# 01-MCU.net
KiCad netlist of a schematic drawn in Altium Designer
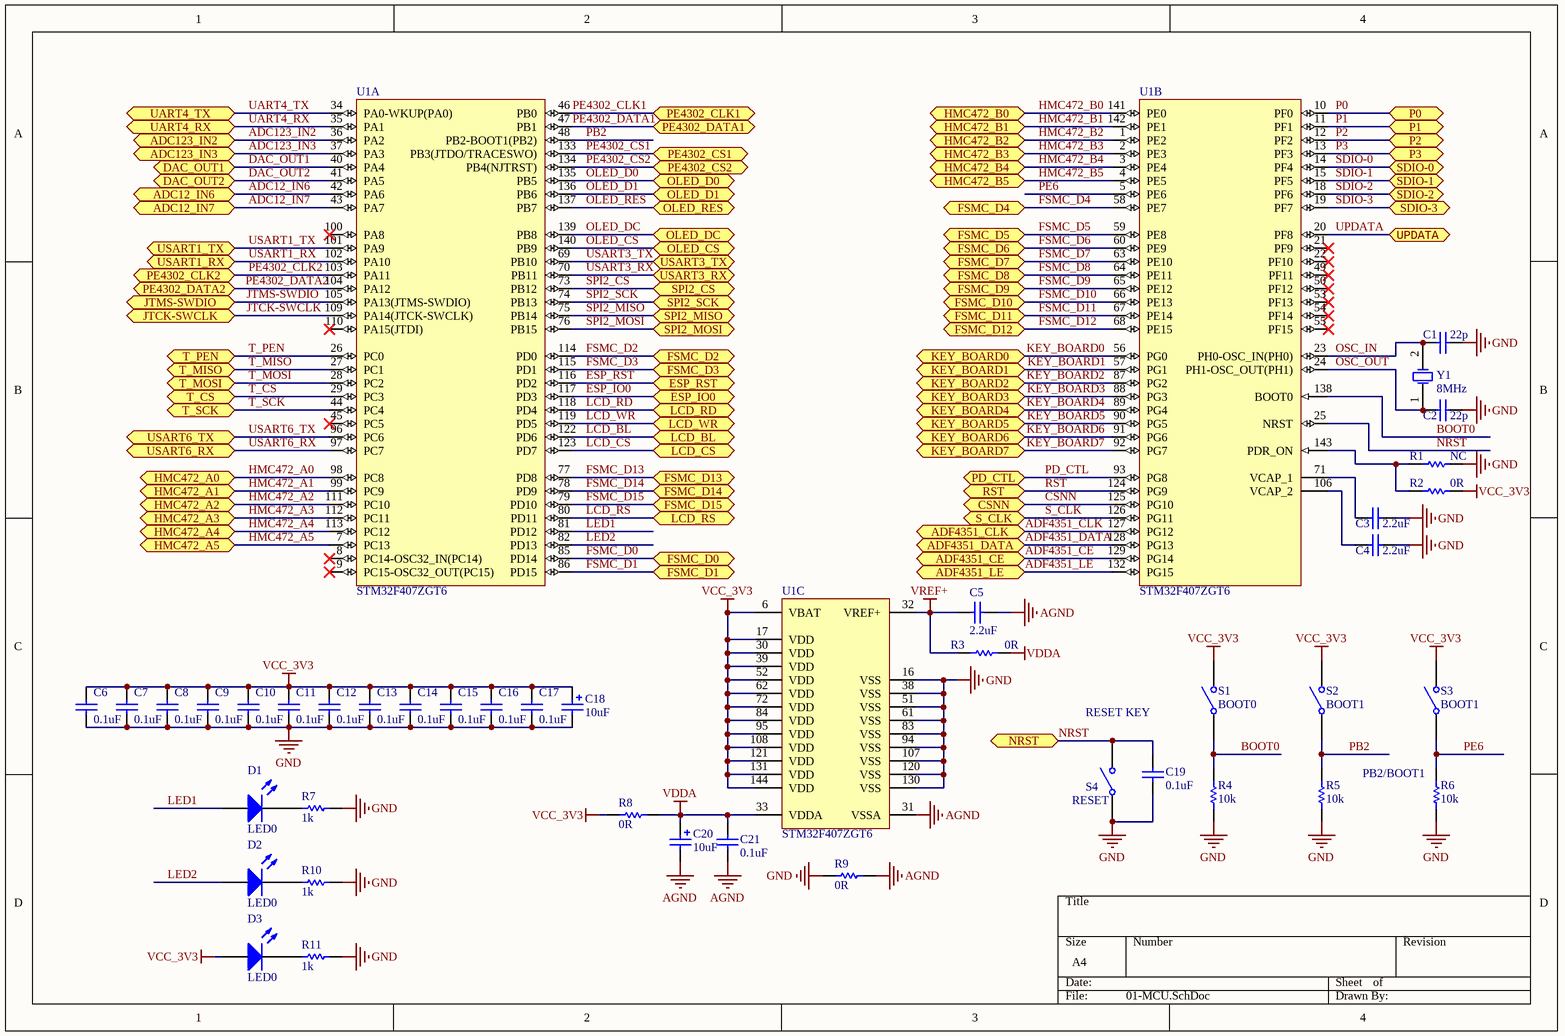
[diagram p0: 01-MCU.SchDoc]

(export (version "E")
  (design (tool "Eeschema 10.0.6"))
  (components
    (comp (ref "C1")
      (value "22p")
      (footprint "0603C")
      (description "CAP CER 10000PF 100V X7R 0603")
      (fields
        (field (name "MANUFACTURER") "TDK Corporation")
        (field (name "MANUFACTURER PART NUMBER") "C1608X7R2A103K080AA")
      )
      (libsource (lib "Desiger_Schlib") (part "Cap1"))
    )
    (comp (ref "C2")
      (value "22p")
      (footprint "0603C")
      (description "CAP CER 10000PF 100V X7R 0603")
      (fields
        (field (name "MANUFACTURER") "TDK Corporation")
        (field (name "MANUFACTURER PART NUMBER") "C1608X7R2A103K080AA")
      )
      (libsource (lib "Desiger_Schlib") (part "Cap1"))
    )
    (comp (ref "C3")
      (value "2.2uF")
      (footprint "0603C")
      (description "CAP CER 10000PF 100V X7R 0603")
      (fields
        (field (name "MANUFACTURER") "TDK Corporation")
        (field (name "MANUFACTURER PART NUMBER") "C1608X7R2A103K080AA")
      )
      (libsource (lib "Desiger_Schlib") (part "Cap1"))
    )
    (comp (ref "C4")
      (value "2.2uF")
      (footprint "0603C")
      (description "CAP CER 10000PF 100V X7R 0603")
      (fields
        (field (name "MANUFACTURER") "TDK Corporation")
        (field (name "MANUFACTURER PART NUMBER") "C1608X7R2A103K080AA")
      )
      (libsource (lib "Desiger_Schlib") (part "Cap1"))
    )
    (comp (ref "C5")
      (value "2.2uF")
      (footprint "0603C")
      (description "CAP CER 10000PF 100V X7R 0603")
      (fields
        (field (name "MANUFACTURER") "TDK Corporation")
        (field (name "MANUFACTURER PART NUMBER") "C1608X7R2A103K080AA")
      )
      (libsource (lib "Desiger_Schlib") (part "Cap1"))
    )
    (comp (ref "C6")
      (value "0.1uF")
      (footprint "0603C")
      (description "CAP CER 10000PF 100V X7R 0603")
      (fields
        (field (name "MANUFACTURER") "TDK Corporation")
        (field (name "MANUFACTURER PART NUMBER") "C1608X7R2A103K080AA")
      )
      (libsource (lib "Desiger_Schlib") (part "Cap1"))
    )
    (comp (ref "C7")
      (value "0.1uF")
      (footprint "0603C")
      (description "CAP CER 10000PF 100V X7R 0603")
      (fields
        (field (name "MANUFACTURER") "TDK Corporation")
        (field (name "MANUFACTURER PART NUMBER") "C1608X7R2A103K080AA")
      )
      (libsource (lib "Desiger_Schlib") (part "Cap1"))
    )
    (comp (ref "C8")
      (value "0.1uF")
      (footprint "0603C")
      (description "CAP CER 10000PF 100V X7R 0603")
      (fields
        (field (name "MANUFACTURER") "TDK Corporation")
        (field (name "MANUFACTURER PART NUMBER") "C1608X7R2A103K080AA")
      )
      (libsource (lib "Desiger_Schlib") (part "Cap1"))
    )
    (comp (ref "C9")
      (value "0.1uF")
      (footprint "0603C")
      (description "CAP CER 10000PF 100V X7R 0603")
      (fields
        (field (name "MANUFACTURER") "TDK Corporation")
        (field (name "MANUFACTURER PART NUMBER") "C1608X7R2A103K080AA")
      )
      (libsource (lib "Desiger_Schlib") (part "Cap1"))
    )
    (comp (ref "C10")
      (value "0.1uF")
      (footprint "0603C")
      (description "CAP CER 10000PF 100V X7R 0603")
      (fields
        (field (name "MANUFACTURER") "TDK Corporation")
        (field (name "MANUFACTURER PART NUMBER") "C1608X7R2A103K080AA")
      )
      (libsource (lib "Desiger_Schlib") (part "Cap1"))
    )
    (comp (ref "C11")
      (value "0.1uF")
      (footprint "0603C")
      (description "CAP CER 10000PF 100V X7R 0603")
      (fields
        (field (name "MANUFACTURER") "TDK Corporation")
        (field (name "MANUFACTURER PART NUMBER") "C1608X7R2A103K080AA")
      )
      (libsource (lib "Desiger_Schlib") (part "Cap1"))
    )
    (comp (ref "C12")
      (value "0.1uF")
      (footprint "0603C")
      (description "CAP CER 10000PF 100V X7R 0603")
      (fields
        (field (name "MANUFACTURER") "TDK Corporation")
        (field (name "MANUFACTURER PART NUMBER") "C1608X7R2A103K080AA")
      )
      (libsource (lib "Desiger_Schlib") (part "Cap1"))
    )
    (comp (ref "C13")
      (value "0.1uF")
      (footprint "0603C")
      (description "CAP CER 10000PF 100V X7R 0603")
      (fields
        (field (name "MANUFACTURER") "TDK Corporation")
        (field (name "MANUFACTURER PART NUMBER") "C1608X7R2A103K080AA")
      )
      (libsource (lib "Desiger_Schlib") (part "Cap1"))
    )
    (comp (ref "C14")
      (value "0.1uF")
      (footprint "0603C")
      (description "CAP CER 10000PF 100V X7R 0603")
      (fields
        (field (name "MANUFACTURER") "TDK Corporation")
        (field (name "MANUFACTURER PART NUMBER") "C1608X7R2A103K080AA")
      )
      (libsource (lib "Desiger_Schlib") (part "Cap1"))
    )
    (comp (ref "C15")
      (value "0.1uF")
      (footprint "0603C")
      (description "CAP CER 10000PF 100V X7R 0603")
      (fields
        (field (name "MANUFACTURER") "TDK Corporation")
        (field (name "MANUFACTURER PART NUMBER") "C1608X7R2A103K080AA")
      )
      (libsource (lib "Desiger_Schlib") (part "Cap1"))
    )
    (comp (ref "C16")
      (value "0.1uF")
      (footprint "0603C")
      (description "CAP CER 10000PF 100V X7R 0603")
      (fields
        (field (name "MANUFACTURER") "TDK Corporation")
        (field (name "MANUFACTURER PART NUMBER") "C1608X7R2A103K080AA")
      )
      (libsource (lib "Desiger_Schlib") (part "Cap1"))
    )
    (comp (ref "C17")
      (value "0.1uF")
      (footprint "0603C")
      (description "CAP CER 10000PF 100V X7R 0603")
      (fields
        (field (name "MANUFACTURER") "TDK Corporation")
        (field (name "MANUFACTURER PART NUMBER") "C1608X7R2A103K080AA")
      )
      (libsource (lib "Desiger_Schlib") (part "Cap1"))
    )
    (comp (ref "C18")
      (value "10uF")
      (footprint "1206T")
      (description "CAP TANT 10UF 10V 10% 1206")
      (fields
        (field (name "MANUFACTURER") "KEMET")
        (field (name "MANUFACTURER PART NUMBER") "T491A106K010AT7280")
      )
      (libsource (lib "Desiger_Schlib") (part "Cap2"))
    )
    (comp (ref "C19")
      (value "0.1uF")
      (footprint "0603C")
      (description "CAP CER 10000PF 100V X7R 0603")
      (fields
        (field (name "MANUFACTURER") "TDK Corporation")
        (field (name "MANUFACTURER PART NUMBER") "C1608X7R2A103K080AA")
      )
      (libsource (lib "Desiger_Schlib") (part "Cap1"))
    )
    (comp (ref "C20")
      (value "10uF")
      (footprint "1206T")
      (description "CAP TANT 10UF 10V 10% 1206")
      (fields
        (field (name "MANUFACTURER") "KEMET")
        (field (name "MANUFACTURER PART NUMBER") "T491A106K010AT7280")
      )
      (libsource (lib "Desiger_Schlib") (part "Cap2"))
    )
    (comp (ref "C21")
      (value "0.1uF")
      (footprint "0603C")
      (description "CAP CER 10000PF 100V X7R 0603")
      (fields
        (field (name "MANUFACTURER") "TDK Corporation")
        (field (name "MANUFACTURER PART NUMBER") "C1608X7R2A103K080AA")
      )
      (libsource (lib "Desiger_Schlib") (part "Cap1"))
    )
    (comp (ref "D1")
      (value "LED0")
      (footprint "0603D")
      (description "Typical INFRARED GaAs LED")
      (fields (field (name "PUBLISHER") "Altium Limited"))
      (libsource (lib "Miscellaneous Devices") (part "LED0"))
    )
    (comp (ref "D2")
      (value "LED0")
      (footprint "0603D")
      (description "Typical INFRARED GaAs LED")
      (fields (field (name "PUBLISHER") "Altium Limited"))
      (libsource (lib "Miscellaneous Devices") (part "LED0"))
    )
    (comp (ref "D3")
      (value "LED0")
      (footprint "0603D")
      (description "Typical INFRARED GaAs LED")
      (fields (field (name "PUBLISHER") "Altium Limited"))
      (libsource (lib "Miscellaneous Devices") (part "LED0"))
    )
    (comp (ref "R1")
      (value "NC")
      (footprint "0603R")
      (description "RES SMD 1K OHM 0.5% 1/16W 0603")
      (fields
        (field (name "MANUFACTURER") "Susumu")
        (field (name "MANUFACTURER PART NUMBER") "RR0816P-102-D")
      )
      (libsource (lib "Desiger_Schlib") (part "Res1"))
    )
    (comp (ref "R2")
      (value "0R")
      (footprint "0603R")
      (description "RES SMD 1K OHM 0.5% 1/16W 0603")
      (fields
        (field (name "MANUFACTURER") "Susumu")
        (field (name "MANUFACTURER PART NUMBER") "RR0816P-102-D")
      )
      (libsource (lib "Desiger_Schlib") (part "Res1"))
    )
    (comp (ref "R3")
      (value "0R")
      (footprint "0603R")
      (description "RES SMD 1K OHM 0.5% 1/16W 0603")
      (fields
        (field (name "MANUFACTURER") "Susumu")
        (field (name "MANUFACTURER PART NUMBER") "RR0816P-102-D")
      )
      (libsource (lib "Desiger_Schlib") (part "Res1"))
    )
    (comp (ref "R4")
      (value "10k")
      (footprint "0603R")
      (description "RES SMD 1K OHM 0.5% 1/16W 0603")
      (fields
        (field (name "MANUFACTURER") "Susumu")
        (field (name "MANUFACTURER PART NUMBER") "RR0816P-102-D")
      )
      (libsource (lib "Desiger_Schlib") (part "Res1"))
    )
    (comp (ref "R5")
      (value "10k")
      (footprint "0603R")
      (description "RES SMD 1K OHM 0.5% 1/16W 0603")
      (fields
        (field (name "MANUFACTURER") "Susumu")
        (field (name "MANUFACTURER PART NUMBER") "RR0816P-102-D")
      )
      (libsource (lib "Desiger_Schlib") (part "Res1"))
    )
    (comp (ref "R6")
      (value "10k")
      (footprint "0603R")
      (description "RES SMD 1K OHM 0.5% 1/16W 0603")
      (fields
        (field (name "MANUFACTURER") "Susumu")
        (field (name "MANUFACTURER PART NUMBER") "RR0816P-102-D")
      )
      (libsource (lib "Desiger_Schlib") (part "Res1"))
    )
    (comp (ref "R7")
      (value "1k")
      (footprint "0603R")
      (description "RES SMD 1K OHM 0.5% 1/16W 0603")
      (fields
        (field (name "MANUFACTURER") "Susumu")
        (field (name "MANUFACTURER PART NUMBER") "RR0816P-102-D")
      )
      (libsource (lib "Desiger_Schlib") (part "Res1"))
    )
    (comp (ref "R8")
      (value "0R")
      (footprint "0603R")
      (description "RES SMD 1K OHM 0.5% 1/16W 0603")
      (fields
        (field (name "MANUFACTURER") "Susumu")
        (field (name "MANUFACTURER PART NUMBER") "RR0816P-102-D")
      )
      (libsource (lib "Desiger_Schlib") (part "Res1"))
    )
    (comp (ref "R9")
      (value "0R")
      (footprint "0603R")
      (description "RES SMD 1K OHM 0.5% 1/16W 0603")
      (fields
        (field (name "MANUFACTURER") "Susumu")
        (field (name "MANUFACTURER PART NUMBER") "RR0816P-102-D")
      )
      (libsource (lib "Desiger_Schlib") (part "Res1"))
    )
    (comp (ref "R10")
      (value "1k")
      (footprint "0603R")
      (description "RES SMD 1K OHM 0.5% 1/16W 0603")
      (fields
        (field (name "MANUFACTURER") "Susumu")
        (field (name "MANUFACTURER PART NUMBER") "RR0816P-102-D")
      )
      (libsource (lib "Desiger_Schlib") (part "Res1"))
    )
    (comp (ref "R11")
      (value "1k")
      (footprint "0603R")
      (description "RES SMD 1K OHM 0.5% 1/16W 0603")
      (fields
        (field (name "MANUFACTURER") "Susumu")
        (field (name "MANUFACTURER PART NUMBER") "RR0816P-102-D")
      )
      (libsource (lib "Desiger_Schlib") (part "Res1"))
    )
    (comp (ref "S1")
      (value "BOOT0")
      (footprint "micro button_2_SMD")
      (description "Single-Pole, Single-Throw Switch")
      (fields (field (name "PUBLISHER") "Altium Limited"))
      (libsource (lib "Miscellaneous Devices") (part "SW-SPST"))
    )
    (comp (ref "S2")
      (value "BOOT1")
      (footprint "micro button_2_SMD")
      (description "Single-Pole, Single-Throw Switch")
      (fields (field (name "PUBLISHER") "Altium Limited"))
      (libsource (lib "Miscellaneous Devices") (part "SW-SPST"))
    )
    (comp (ref "S3")
      (value "BOOT1")
      (footprint "micro button_2_SMD")
      (description "Single-Pole, Single-Throw Switch")
      (fields (field (name "PUBLISHER") "Altium Limited"))
      (libsource (lib "Miscellaneous Devices") (part "SW-SPST"))
    )
    (comp (ref "S4")
      (value "RESET")
      (footprint "micro button_2_SMD")
      (description "Single-Pole, Single-Throw Switch")
      (fields (field (name "PUBLISHER") "Altium Limited"))
      (libsource (lib "Miscellaneous Devices") (part "SW-SPST"))
    )
    (comp (ref "U1")
      (value "STM32F407ZGT6")
      (footprint "QFP144-0r5-20X20")
      (fields (field (name "MANUFACTURER") "STMicroelectronics"))
      (libsource (lib "STMicroelectronics STM32 F4") (part "STM32F407ZGT6"))
    )
    (comp (ref "Y1")
      (value "8MHz")
      (footprint "CO2-4R75X11R4-S")
      (description "Crystal Oscillator")
      (fields (field (name "PUBLISHER") "Altium Limited"))
      (libsource (lib "Miscellaneous Devices") (part "XTAL"))
    )
  )
  (nets
    (net (code "1") (name "/ADC12_IN6") (class "Default")
      (node (ref "U1") (pin "42") (pinfunction "PA6_42") (pintype "bidirectional"))
    )
    (net (code "2") (name "/ADC12_IN7") (class "Default")
      (node (ref "U1") (pin "43") (pinfunction "PA7_43") (pintype "bidirectional"))
    )
    (net (code "3") (name "/ADC123_IN2") (class "Default")
      (node (ref "U1") (pin "36") (pinfunction "PA2_36") (pintype "bidirectional"))
    )
    (net (code "4") (name "/ADC123_IN3") (class "Default")
      (node (ref "U1") (pin "37") (pinfunction "PA3_37") (pintype "bidirectional"))
    )
    (net (code "5") (name "/ADF4351_CE") (class "Default")
      (node (ref "U1") (pin "129") (pinfunction "PG14_129") (pintype "bidirectional"))
    )
    (net (code "6") (name "/ADF4351_CLK") (class "Default")
      (node (ref "U1") (pin "127") (pinfunction "PG12_127") (pintype "bidirectional"))
    )
    (net (code "7") (name "/ADF4351_DATA") (class "Default")
      (node (ref "U1") (pin "128") (pinfunction "PG13_128") (pintype "bidirectional"))
    )
    (net (code "8") (name "/ADF4351_LE") (class "Default")
      (node (ref "U1") (pin "132") (pinfunction "PG15_132") (pintype "bidirectional"))
    )
    (net (code "9") (name "/BOOT0") (class "Default")
      (node (ref "R4") (pin "2") (pinfunction "2_2") (pintype "passive"))
      (node (ref "S1") (pin "1") (pinfunction "COMMON_1") (pintype "passive"))
      (node (ref "U1") (pin "138") (pinfunction "BOOT0_138") (pintype "input"))
    )
    (net (code "10") (name "/CSNN") (class "Default")
      (node (ref "U1") (pin "125") (pinfunction "PG10_125") (pintype "bidirectional"))
    )
    (net (code "11") (name "/DAC_OUT1") (class "Default")
      (node (ref "U1") (pin "40") (pinfunction "PA4_40") (pintype "bidirectional"))
    )
    (net (code "12") (name "/DAC_OUT2") (class "Default")
      (node (ref "U1") (pin "41") (pinfunction "PA5_41") (pintype "bidirectional"))
    )
    (net (code "13") (name "/ESP_IO0") (class "Default")
      (node (ref "U1") (pin "117") (pinfunction "PD3_117") (pintype "bidirectional"))
    )
    (net (code "14") (name "/ESP_RST") (class "Default")
      (node (ref "U1") (pin "116") (pinfunction "PD2_116") (pintype "bidirectional"))
    )
    (net (code "15") (name "/FSMC_D0") (class "Default")
      (node (ref "U1") (pin "85") (pinfunction "PD14_85") (pintype "bidirectional"))
    )
    (net (code "16") (name "/FSMC_D1") (class "Default")
      (node (ref "U1") (pin "86") (pinfunction "PD15_86") (pintype "bidirectional"))
    )
    (net (code "17") (name "/FSMC_D2") (class "Default")
      (node (ref "U1") (pin "114") (pinfunction "PD0_114") (pintype "bidirectional"))
    )
    (net (code "18") (name "/FSMC_D3") (class "Default")
      (node (ref "U1") (pin "115") (pinfunction "PD1_115") (pintype "bidirectional"))
    )
    (net (code "19") (name "/FSMC_D4") (class "Default")
      (node (ref "U1") (pin "58") (pinfunction "PE7_58") (pintype "bidirectional"))
    )
    (net (code "20") (name "/FSMC_D5") (class "Default")
      (node (ref "U1") (pin "59") (pinfunction "PE8_59") (pintype "bidirectional"))
    )
    (net (code "21") (name "/FSMC_D6") (class "Default")
      (node (ref "U1") (pin "60") (pinfunction "PE9_60") (pintype "bidirectional"))
    )
    (net (code "22") (name "/FSMC_D7") (class "Default")
      (node (ref "U1") (pin "63") (pinfunction "PE10_63") (pintype "bidirectional"))
    )
    (net (code "23") (name "/FSMC_D8") (class "Default")
      (node (ref "U1") (pin "64") (pinfunction "PE11_64") (pintype "bidirectional"))
    )
    (net (code "24") (name "/FSMC_D9") (class "Default")
      (node (ref "U1") (pin "65") (pinfunction "PE12_65") (pintype "bidirectional"))
    )
    (net (code "25") (name "/FSMC_D10") (class "Default")
      (node (ref "U1") (pin "66") (pinfunction "PE13_66") (pintype "bidirectional"))
    )
    (net (code "26") (name "/FSMC_D11") (class "Default")
      (node (ref "U1") (pin "67") (pinfunction "PE14_67") (pintype "bidirectional"))
    )
    (net (code "27") (name "/FSMC_D12") (class "Default")
      (node (ref "U1") (pin "68") (pinfunction "PE15_68") (pintype "bidirectional"))
    )
    (net (code "28") (name "/FSMC_D13") (class "Default")
      (node (ref "U1") (pin "77") (pinfunction "PD8_77") (pintype "bidirectional"))
    )
    (net (code "29") (name "/FSMC_D14") (class "Default")
      (node (ref "U1") (pin "78") (pinfunction "PD9_78") (pintype "bidirectional"))
    )
    (net (code "30") (name "/FSMC_D15") (class "Default")
      (node (ref "U1") (pin "79") (pinfunction "PD10_79") (pintype "bidirectional"))
    )
    (net (code "31") (name "/HMC472_A0") (class "Default")
      (node (ref "U1") (pin "98") (pinfunction "PC8_98") (pintype "bidirectional"))
    )
    (net (code "32") (name "/HMC472_A1") (class "Default")
      (node (ref "U1") (pin "99") (pinfunction "PC9_99") (pintype "bidirectional"))
    )
    (net (code "33") (name "/HMC472_A2") (class "Default")
      (node (ref "U1") (pin "111") (pinfunction "PC10_111") (pintype "bidirectional"))
    )
    (net (code "34") (name "/HMC472_A3") (class "Default")
      (node (ref "U1") (pin "112") (pinfunction "PC11_112") (pintype "bidirectional"))
    )
    (net (code "35") (name "/HMC472_A4") (class "Default")
      (node (ref "U1") (pin "113") (pinfunction "PC12_113") (pintype "bidirectional"))
    )
    (net (code "36") (name "/HMC472_A5") (class "Default")
      (node (ref "U1") (pin "7") (pinfunction "PC13_7") (pintype "bidirectional"))
    )
    (net (code "37") (name "/HMC472_B0") (class "Default")
      (node (ref "U1") (pin "141") (pinfunction "PE0_141") (pintype "bidirectional"))
    )
    (net (code "38") (name "/HMC472_B1") (class "Default")
      (node (ref "U1") (pin "142") (pinfunction "PE1_142") (pintype "bidirectional"))
    )
    (net (code "39") (name "/HMC472_B2") (class "Default")
      (node (ref "U1") (pin "1") (pinfunction "PE2_1") (pintype "bidirectional"))
    )
    (net (code "40") (name "/HMC472_B3") (class "Default")
      (node (ref "U1") (pin "2") (pinfunction "PE3_2") (pintype "bidirectional"))
    )
    (net (code "41") (name "/HMC472_B4") (class "Default")
      (node (ref "U1") (pin "3") (pinfunction "PE4_3") (pintype "bidirectional"))
    )
    (net (code "42") (name "/HMC472_B5") (class "Default")
      (node (ref "U1") (pin "4") (pinfunction "PE5_4") (pintype "bidirectional"))
    )
    (net (code "43") (name "/JTCK-SWCLK") (class "Default")
      (node (ref "U1") (pin "109") (pinfunction "PA14(JTCK-SWCLK)_109") (pintype "bidirectional"))
    )
    (net (code "44") (name "/JTMS-SWDIO") (class "Default")
      (node (ref "U1") (pin "105") (pinfunction "PA13(JTMS-SWDIO)_105") (pintype "bidirectional"))
    )
    (net (code "45") (name "/KEY_BOARD0") (class "Default")
      (node (ref "U1") (pin "56") (pinfunction "PG0_56") (pintype "bidirectional"))
    )
    (net (code "46") (name "/KEY_BOARD1") (class "Default")
      (node (ref "U1") (pin "57") (pinfunction "PG1_57") (pintype "bidirectional"))
    )
    (net (code "47") (name "/KEY_BOARD2") (class "Default")
      (node (ref "U1") (pin "87") (pinfunction "PG2_87") (pintype "bidirectional"))
    )
    (net (code "48") (name "/KEY_BOARD3") (class "Default")
      (node (ref "U1") (pin "88") (pinfunction "PG3_88") (pintype "bidirectional"))
    )
    (net (code "49") (name "/KEY_BOARD4") (class "Default")
      (node (ref "U1") (pin "89") (pinfunction "PG4_89") (pintype "bidirectional"))
    )
    (net (code "50") (name "/KEY_BOARD5") (class "Default")
      (node (ref "U1") (pin "90") (pinfunction "PG5_90") (pintype "bidirectional"))
    )
    (net (code "51") (name "/KEY_BOARD6") (class "Default")
      (node (ref "U1") (pin "91") (pinfunction "PG6_91") (pintype "bidirectional"))
    )
    (net (code "52") (name "/KEY_BOARD7") (class "Default")
      (node (ref "U1") (pin "92") (pinfunction "PG7_92") (pintype "bidirectional"))
    )
    (net (code "53") (name "/LCD_BL") (class "Default")
      (node (ref "U1") (pin "122") (pinfunction "PD6_122") (pintype "bidirectional"))
    )
    (net (code "54") (name "/LCD_CS") (class "Default")
      (node (ref "U1") (pin "123") (pinfunction "PD7_123") (pintype "bidirectional"))
    )
    (net (code "55") (name "/LCD_RD") (class "Default")
      (node (ref "U1") (pin "118") (pinfunction "PD4_118") (pintype "bidirectional"))
    )
    (net (code "56") (name "/LCD_RS") (class "Default")
      (node (ref "U1") (pin "80") (pinfunction "PD11_80") (pintype "bidirectional"))
    )
    (net (code "57") (name "/LCD_WR") (class "Default")
      (node (ref "U1") (pin "119") (pinfunction "PD5_119") (pintype "bidirectional"))
    )
    (net (code "58") (name "/LED1") (class "Default")
      (node (ref "D1") (pin "1") (pinfunction "A_1") (pintype "passive"))
      (node (ref "U1") (pin "81") (pinfunction "PD12_81") (pintype "bidirectional"))
    )
    (net (code "59") (name "/LED2") (class "Default")
      (node (ref "D2") (pin "1") (pinfunction "A_1") (pintype "passive"))
      (node (ref "U1") (pin "82") (pinfunction "PD13_82") (pintype "bidirectional"))
    )
    (net (code "60") (name "/NRST") (class "Default")
      (node (ref "C19") (pin "2") (pinfunction "2_2") (pintype "passive"))
      (node (ref "S4") (pin "2") (pinfunction "NO_2") (pintype "passive"))
      (node (ref "U1") (pin "25") (pinfunction "NRST_25") (pintype "bidirectional"))
    )
    (net (code "61") (name "/OLED_CS") (class "Default")
      (node (ref "U1") (pin "140") (pinfunction "PB9_140") (pintype "bidirectional"))
    )
    (net (code "62") (name "/OLED_D0") (class "Default")
      (node (ref "U1") (pin "135") (pinfunction "PB5_135") (pintype "bidirectional"))
    )
    (net (code "63") (name "/OLED_D1") (class "Default")
      (node (ref "U1") (pin "136") (pinfunction "PB6_136") (pintype "bidirectional"))
    )
    (net (code "64") (name "/OLED_DC") (class "Default")
      (node (ref "U1") (pin "139") (pinfunction "PB8_139") (pintype "bidirectional"))
    )
    (net (code "65") (name "/OLED_RES") (class "Default")
      (node (ref "U1") (pin "137") (pinfunction "PB7_137") (pintype "bidirectional"))
    )
    (net (code "66") (name "/OSC_IN") (class "Default")
      (node (ref "C1") (pin "1") (pinfunction "1_1") (pintype "passive"))
      (node (ref "U1") (pin "23") (pinfunction "PH0-OSC_IN(PH0)_23") (pintype "bidirectional"))
      (node (ref "Y1") (pin "2") (pinfunction "OSC2_2") (pintype "passive"))
    )
    (net (code "67") (name "/OSC_OUT") (class "Default")
      (node (ref "C2") (pin "1") (pinfunction "1_1") (pintype "passive"))
      (node (ref "U1") (pin "24") (pinfunction "PH1-OSC_OUT(PH1)_24") (pintype "bidirectional"))
      (node (ref "Y1") (pin "1") (pinfunction "OSC1_1") (pintype "passive"))
    )
    (net (code "68") (name "/P0") (class "Default")
      (node (ref "U1") (pin "10") (pinfunction "PF0_10") (pintype "bidirectional"))
    )
    (net (code "69") (name "/P1") (class "Default")
      (node (ref "U1") (pin "11") (pinfunction "PF1_11") (pintype "bidirectional"))
    )
    (net (code "70") (name "/P2") (class "Default")
      (node (ref "U1") (pin "12") (pinfunction "PF2_12") (pintype "bidirectional"))
    )
    (net (code "71") (name "/P3") (class "Default")
      (node (ref "U1") (pin "13") (pinfunction "PF3_13") (pintype "bidirectional"))
    )
    (net (code "72") (name "/PB2") (class "Default")
      (node (ref "R5") (pin "2") (pinfunction "2_2") (pintype "passive"))
      (node (ref "S2") (pin "1") (pinfunction "COMMON_1") (pintype "passive"))
      (node (ref "U1") (pin "48") (pinfunction "PB2-BOOT1(PB2)_48") (pintype "bidirectional"))
    )
    (net (code "73") (name "/PD_CTL") (class "Default")
      (node (ref "U1") (pin "93") (pinfunction "PG8_93") (pintype "bidirectional"))
    )
    (net (code "74") (name "/PE6") (class "Default")
      (node (ref "R6") (pin "2") (pinfunction "2_2") (pintype "passive"))
      (node (ref "S3") (pin "1") (pinfunction "COMMON_1") (pintype "passive"))
      (node (ref "U1") (pin "5") (pinfunction "PE6_5") (pintype "bidirectional"))
    )
    (net (code "75") (name "/PE4302_CLK1") (class "Default")
      (node (ref "U1") (pin "46") (pinfunction "PB0_46") (pintype "bidirectional"))
    )
    (net (code "76") (name "/PE4302_CLK2") (class "Default")
      (node (ref "U1") (pin "103") (pinfunction "PA11_103") (pintype "bidirectional"))
    )
    (net (code "77") (name "/PE4302_CS1") (class "Default")
      (node (ref "U1") (pin "133") (pinfunction "PB3(JTDO/TRACESWO)_133") (pintype "bidirectional"))
    )
    (net (code "78") (name "/PE4302_CS2") (class "Default")
      (node (ref "U1") (pin "134") (pinfunction "PB4(NJTRST)_134") (pintype "bidirectional"))
    )
    (net (code "79") (name "/PE4302_DATA1") (class "Default")
      (node (ref "U1") (pin "47") (pinfunction "PB1_47") (pintype "bidirectional"))
    )
    (net (code "80") (name "/PE4302_DATA2") (class "Default")
      (node (ref "U1") (pin "104") (pinfunction "PA12_104") (pintype "bidirectional"))
    )
    (net (code "81") (name "/RST") (class "Default")
      (node (ref "U1") (pin "124") (pinfunction "PG9_124") (pintype "bidirectional"))
    )
    (net (code "82") (name "/SDIO-0") (class "Default")
      (node (ref "U1") (pin "14") (pinfunction "PF4_14") (pintype "bidirectional"))
    )
    (net (code "83") (name "/SDIO-1") (class "Default")
      (node (ref "U1") (pin "15") (pinfunction "PF5_15") (pintype "bidirectional"))
    )
    (net (code "84") (name "/SDIO-2") (class "Default")
      (node (ref "U1") (pin "18") (pinfunction "PF6_18") (pintype "bidirectional"))
    )
    (net (code "85") (name "/SDIO-3") (class "Default")
      (node (ref "U1") (pin "19") (pinfunction "PF7_19") (pintype "bidirectional"))
    )
    (net (code "86") (name "/SPI2_CS") (class "Default")
      (node (ref "U1") (pin "73") (pinfunction "PB12_73") (pintype "bidirectional"))
    )
    (net (code "87") (name "/SPI2_MISO") (class "Default")
      (node (ref "U1") (pin "75") (pinfunction "PB14_75") (pintype "bidirectional"))
    )
    (net (code "88") (name "/SPI2_MOSI") (class "Default")
      (node (ref "U1") (pin "76") (pinfunction "PB15_76") (pintype "bidirectional"))
    )
    (net (code "89") (name "/SPI2_SCK") (class "Default")
      (node (ref "U1") (pin "74") (pinfunction "PB13_74") (pintype "bidirectional"))
    )
    (net (code "90") (name "/S_CLK") (class "Default")
      (node (ref "U1") (pin "126") (pinfunction "PG11_126") (pintype "bidirectional"))
    )
    (net (code "91") (name "/T_CS") (class "Default")
      (node (ref "U1") (pin "29") (pinfunction "PC3_29") (pintype "bidirectional"))
    )
    (net (code "92") (name "/T_MISO") (class "Default")
      (node (ref "U1") (pin "27") (pinfunction "PC1_27") (pintype "bidirectional"))
    )
    (net (code "93") (name "/T_MOSI") (class "Default")
      (node (ref "U1") (pin "28") (pinfunction "PC2_28") (pintype "bidirectional"))
    )
    (net (code "94") (name "/T_PEN") (class "Default")
      (node (ref "U1") (pin "26") (pinfunction "PC0_26") (pintype "bidirectional"))
    )
    (net (code "95") (name "/T_SCK") (class "Default")
      (node (ref "U1") (pin "44") (pinfunction "PC4_44") (pintype "bidirectional"))
    )
    (net (code "96") (name "/UART4_RX") (class "Default")
      (node (ref "U1") (pin "35") (pinfunction "PA1_35") (pintype "bidirectional"))
    )
    (net (code "97") (name "/UART4_TX") (class "Default")
      (node (ref "U1") (pin "34") (pinfunction "PA0-WKUP(PA0)_34") (pintype "bidirectional"))
    )
    (net (code "98") (name "/UPDATA") (class "Default")
      (node (ref "U1") (pin "20") (pinfunction "PF8_20") (pintype "bidirectional"))
    )
    (net (code "99") (name "/USART1_RX") (class "Default")
      (node (ref "U1") (pin "102") (pinfunction "PA10_102") (pintype "bidirectional"))
    )
    (net (code "100") (name "/USART1_TX") (class "Default")
      (node (ref "U1") (pin "101") (pinfunction "PA9_101") (pintype "bidirectional"))
    )
    (net (code "101") (name "/USART3_RX") (class "Default")
      (node (ref "U1") (pin "70") (pinfunction "PB11_70") (pintype "bidirectional"))
    )
    (net (code "102") (name "/USART3_TX") (class "Default")
      (node (ref "U1") (pin "69") (pinfunction "PB10_69") (pintype "bidirectional"))
    )
    (net (code "103") (name "/USART6_RX") (class "Default")
      (node (ref "U1") (pin "97") (pinfunction "PC7_97") (pintype "bidirectional"))
    )
    (net (code "104") (name "/USART6_TX") (class "Default")
      (node (ref "U1") (pin "96") (pinfunction "PC6_96") (pintype "bidirectional"))
    )
    (net (code "105") (name "AGND") (class "Default")
      (node (ref "C20") (pin "2") (pinfunction "-_2") (pintype "passive"))
      (node (ref "C21") (pin "1") (pinfunction "1_1") (pintype "passive"))
      (node (ref "C5") (pin "1") (pinfunction "1_1") (pintype "passive"))
      (node (ref "R9") (pin "1") (pinfunction "1_1") (pintype "passive"))
      (node (ref "U1") (pin "31") (pinfunction "VSSA_31") (pintype "power_in"))
    )
    (net (code "106") (name "GND") (class "Default")
      (node (ref "C1") (pin "2") (pinfunction "2_2") (pintype "passive"))
      (node (ref "C10") (pin "2") (pinfunction "2_2") (pintype "passive"))
      (node (ref "C11") (pin "2") (pinfunction "2_2") (pintype "passive"))
      (node (ref "C12") (pin "2") (pinfunction "2_2") (pintype "passive"))
      (node (ref "C13") (pin "2") (pinfunction "2_2") (pintype "passive"))
      (node (ref "C14") (pin "2") (pinfunction "2_2") (pintype "passive"))
      (node (ref "C15") (pin "2") (pinfunction "2_2") (pintype "passive"))
      (node (ref "C16") (pin "2") (pinfunction "2_2") (pintype "passive"))
      (node (ref "C17") (pin "2") (pinfunction "2_2") (pintype "passive"))
      (node (ref "C18") (pin "2") (pinfunction "-_2") (pintype "passive"))
      (node (ref "C19") (pin "1") (pinfunction "1_1") (pintype "passive"))
      (node (ref "C2") (pin "2") (pinfunction "2_2") (pintype "passive"))
      (node (ref "C3") (pin "2") (pinfunction "2_2") (pintype "passive"))
      (node (ref "C4") (pin "2") (pinfunction "2_2") (pintype "passive"))
      (node (ref "C6") (pin "2") (pinfunction "2_2") (pintype "passive"))
      (node (ref "C7") (pin "2") (pinfunction "2_2") (pintype "passive"))
      (node (ref "C8") (pin "2") (pinfunction "2_2") (pintype "passive"))
      (node (ref "C9") (pin "2") (pinfunction "2_2") (pintype "passive"))
      (node (ref "R1") (pin "2") (pinfunction "2_2") (pintype "passive"))
      (node (ref "R10") (pin "2") (pinfunction "2_2") (pintype "passive"))
      (node (ref "R11") (pin "2") (pinfunction "2_2") (pintype "passive"))
      (node (ref "R4") (pin "1") (pinfunction "1_1") (pintype "passive"))
      (node (ref "R5") (pin "1") (pinfunction "1_1") (pintype "passive"))
      (node (ref "R6") (pin "1") (pinfunction "1_1") (pintype "passive"))
      (node (ref "R7") (pin "2") (pinfunction "2_2") (pintype "passive"))
      (node (ref "R9") (pin "2") (pinfunction "2_2") (pintype "passive"))
      (node (ref "S4") (pin "1") (pinfunction "COMMON_1") (pintype "passive"))
      (node (ref "U1") (pin "107") (pinfunction "VSS_107") (pintype "power_in"))
      (node (ref "U1") (pin "120") (pinfunction "VSS_120") (pintype "power_in"))
      (node (ref "U1") (pin "130") (pinfunction "VSS_130") (pintype "power_in"))
      (node (ref "U1") (pin "16") (pinfunction "VSS_16") (pintype "power_in"))
      (node (ref "U1") (pin "38") (pinfunction "VSS_38") (pintype "power_in"))
      (node (ref "U1") (pin "51") (pinfunction "VSS_51") (pintype "power_in"))
      (node (ref "U1") (pin "61") (pinfunction "VSS_61") (pintype "power_in"))
      (node (ref "U1") (pin "83") (pinfunction "VSS_83") (pintype "power_in"))
      (node (ref "U1") (pin "94") (pinfunction "VSS_94") (pintype "power_in"))
    )
    (net (code "107") (name "Net-(D1-K)") (class "Default")
      (node (ref "D1") (pin "2") (pinfunction "K_2") (pintype "passive"))
      (node (ref "R7") (pin "1") (pinfunction "1_1") (pintype "passive"))
    )
    (net (code "108") (name "Net-(D2-K)") (class "Default")
      (node (ref "D2") (pin "2") (pinfunction "K_2") (pintype "passive"))
      (node (ref "R10") (pin "1") (pinfunction "1_1") (pintype "passive"))
    )
    (net (code "109") (name "Net-(D3-K)") (class "Default")
      (node (ref "D3") (pin "2") (pinfunction "K_2") (pintype "passive"))
      (node (ref "R11") (pin "1") (pinfunction "1_1") (pintype "passive"))
    )
    (net (code "110") (name "Net-(U1B-PDR_ON)") (class "Default")
      (node (ref "R1") (pin "1") (pinfunction "1_1") (pintype "passive"))
      (node (ref "R2") (pin "1") (pinfunction "1_1") (pintype "passive"))
      (node (ref "U1") (pin "143") (pinfunction "PDR_ON_143") (pintype "input"))
    )
    (net (code "111") (name "Net-(U1B-VCAP_1)") (class "Default")
      (node (ref "C3") (pin "1") (pinfunction "1_1") (pintype "passive"))
      (node (ref "U1") (pin "71") (pinfunction "VCAP_1_71") (pintype "power_in"))
    )
    (net (code "112") (name "Net-(U1B-VCAP_2)") (class "Default")
      (node (ref "C4") (pin "1") (pinfunction "1_1") (pintype "passive"))
      (node (ref "U1") (pin "106") (pinfunction "VCAP_2_106") (pintype "power_in"))
    )
    (net (code "113") (name "VCC_3V3") (class "Default")
      (node (ref "C10") (pin "1") (pinfunction "1_1") (pintype "passive"))
      (node (ref "C11") (pin "1") (pinfunction "1_1") (pintype "passive"))
      (node (ref "C12") (pin "1") (pinfunction "1_1") (pintype "passive"))
      (node (ref "C13") (pin "1") (pinfunction "1_1") (pintype "passive"))
      (node (ref "C14") (pin "1") (pinfunction "1_1") (pintype "passive"))
      (node (ref "C15") (pin "1") (pinfunction "1_1") (pintype "passive"))
      (node (ref "C16") (pin "1") (pinfunction "1_1") (pintype "passive"))
      (node (ref "C17") (pin "1") (pinfunction "1_1") (pintype "passive"))
      (node (ref "C18") (pin "1") (pinfunction "+_1") (pintype "passive"))
      (node (ref "C6") (pin "1") (pinfunction "1_1") (pintype "passive"))
      (node (ref "C7") (pin "1") (pinfunction "1_1") (pintype "passive"))
      (node (ref "C8") (pin "1") (pinfunction "1_1") (pintype "passive"))
      (node (ref "C9") (pin "1") (pinfunction "1_1") (pintype "passive"))
      (node (ref "D3") (pin "1") (pinfunction "A_1") (pintype "passive"))
      (node (ref "R2") (pin "2") (pinfunction "2_2") (pintype "passive"))
      (node (ref "R8") (pin "2") (pinfunction "2_2") (pintype "passive"))
      (node (ref "S1") (pin "2") (pinfunction "NO_2") (pintype "passive"))
      (node (ref "S2") (pin "2") (pinfunction "NO_2") (pintype "passive"))
      (node (ref "S3") (pin "2") (pinfunction "NO_2") (pintype "passive"))
      (node (ref "U1") (pin "108") (pinfunction "VDD_108") (pintype "power_in"))
      (node (ref "U1") (pin "121") (pinfunction "VDD_121") (pintype "power_in"))
      (node (ref "U1") (pin "131") (pinfunction "VDD_131") (pintype "power_in"))
      (node (ref "U1") (pin "144") (pinfunction "VDD_144") (pintype "power_in"))
      (node (ref "U1") (pin "17") (pinfunction "VDD_17") (pintype "power_in"))
      (node (ref "U1") (pin "30") (pinfunction "VDD_30") (pintype "power_in"))
      (node (ref "U1") (pin "39") (pinfunction "VDD_39") (pintype "power_in"))
      (node (ref "U1") (pin "52") (pinfunction "VDD_52") (pintype "power_in"))
      (node (ref "U1") (pin "6") (pinfunction "VBAT_6") (pintype "power_in"))
      (node (ref "U1") (pin "62") (pinfunction "VDD_62") (pintype "power_in"))
      (node (ref "U1") (pin "72") (pinfunction "VDD_72") (pintype "power_in"))
      (node (ref "U1") (pin "84") (pinfunction "VDD_84") (pintype "power_in"))
      (node (ref "U1") (pin "95") (pinfunction "VDD_95") (pintype "power_in"))
    )
    (net (code "114") (name "VDDA") (class "Default")
      (node (ref "C20") (pin "1") (pinfunction "+_1") (pintype "passive"))
      (node (ref "C21") (pin "2") (pinfunction "2_2") (pintype "passive"))
      (node (ref "R3") (pin "1") (pinfunction "1_1") (pintype "passive"))
      (node (ref "R8") (pin "1") (pinfunction "1_1") (pintype "passive"))
      (node (ref "U1") (pin "33") (pinfunction "VDDA_33") (pintype "power_in"))
    )
    (net (code "115") (name "VREF+") (class "Default")
      (node (ref "C5") (pin "2") (pinfunction "2_2") (pintype "passive"))
      (node (ref "R3") (pin "2") (pinfunction "2_2") (pintype "passive"))
      (node (ref "U1") (pin "32") (pinfunction "VREF+_32") (pintype "power_in"))
    )
    (net (code "116") (name "unconnected-(U1A-PA8-Pad100)") (class "Default")
      (node (ref "U1") (pin "100") (pinfunction "PA8_100") (pintype "bidirectional+no_connect"))
    )
    (net (code "117") (name "unconnected-(U1A-PA15(JTDI)-Pad110)") (class "Default")
      (node (ref "U1") (pin "110") (pinfunction "PA15(JTDI)_110") (pintype "bidirectional+no_connect"))
    )
    (net (code "118") (name "unconnected-(U1A-PC5-Pad45)") (class "Default")
      (node (ref "U1") (pin "45") (pinfunction "PC5_45") (pintype "bidirectional+no_connect"))
    )
    (net (code "119") (name "unconnected-(U1A-PC14-OSC32_IN(PC14)-Pad8)") (class "Default")
      (node (ref "U1") (pin "8") (pinfunction "PC14-OSC32_IN(PC14)_8") (pintype "bidirectional+no_connect"))
    )
    (net (code "120") (name "unconnected-(U1A-PC15-OSC32_OUT(PC15)-Pad9)") (class "Default")
      (node (ref "U1") (pin "9") (pinfunction "PC15-OSC32_OUT(PC15)_9") (pintype "bidirectional+no_connect"))
    )
    (net (code "121") (name "unconnected-(U1B-PF9-Pad21)") (class "Default")
      (node (ref "U1") (pin "21") (pinfunction "PF9_21") (pintype "bidirectional+no_connect"))
    )
    (net (code "122") (name "unconnected-(U1B-PF10-Pad22)") (class "Default")
      (node (ref "U1") (pin "22") (pinfunction "PF10_22") (pintype "bidirectional+no_connect"))
    )
    (net (code "123") (name "unconnected-(U1B-PF11-Pad49)") (class "Default")
      (node (ref "U1") (pin "49") (pinfunction "PF11_49") (pintype "bidirectional+no_connect"))
    )
    (net (code "124") (name "unconnected-(U1B-PF12-Pad50)") (class "Default")
      (node (ref "U1") (pin "50") (pinfunction "PF12_50") (pintype "bidirectional+no_connect"))
    )
    (net (code "125") (name "unconnected-(U1B-PF13-Pad53)") (class "Default")
      (node (ref "U1") (pin "53") (pinfunction "PF13_53") (pintype "bidirectional+no_connect"))
    )
    (net (code "126") (name "unconnected-(U1B-PF14-Pad54)") (class "Default")
      (node (ref "U1") (pin "54") (pinfunction "PF14_54") (pintype "bidirectional+no_connect"))
    )
    (net (code "127") (name "unconnected-(U1B-PF15-Pad55)") (class "Default")
      (node (ref "U1") (pin "55") (pinfunction "PF15_55") (pintype "bidirectional+no_connect"))
    )
  )
)
